# BrushlessDriver.net
KiCad netlist of a schematic drawn in Altium Designer
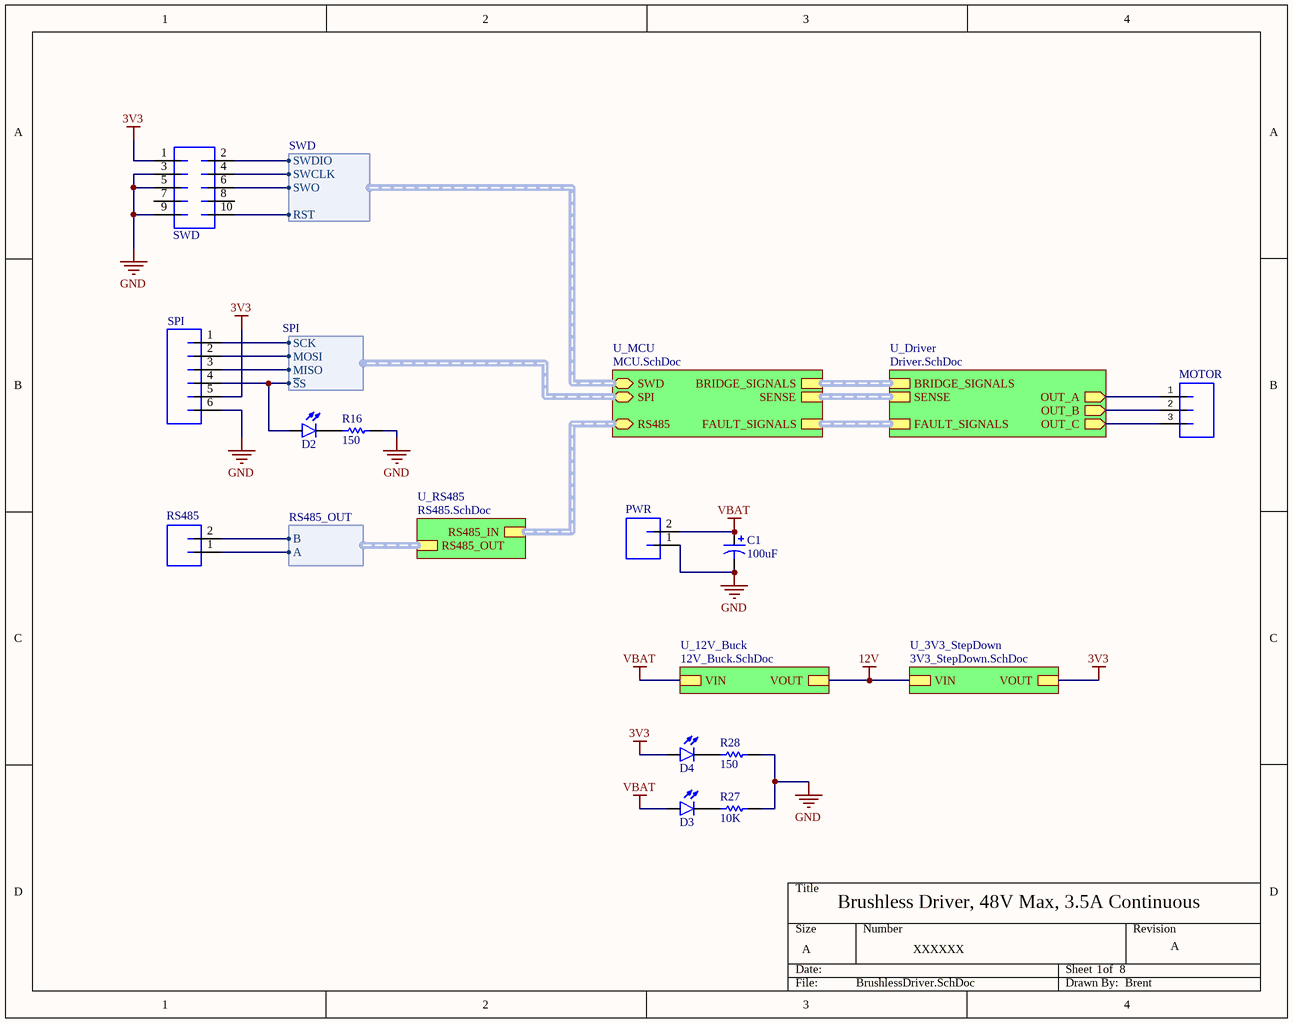
[diagram p0: BrushlessDriver.SchDoc]

(export (version "E")
  (design (tool "Eeschema 10.0.6"))
  (components
    (comp (ref "C1")
      (value "100uF")
      (footprint "CAP-ELECTROLYTIC[10.0x12.6]")
      (description "100uF 63V 20%")
      (fields (field (name "PARTNUMBER") "PCR1J101MCL1GS") (field (name "MANUFACTURER") "Nichicon"))
      (libsource (lib "Capacitors") (part "CAP_100uF_63V_20%"))
    )
    (comp (ref "D2")
      (value "LED_0603_GREEN_5mA")
      (footprint "LED0603")
      (fields (field (name "PARTNUMBER") "LTST-C193TGKT-5A") (field (name "MANUFACTURER") "Lite-On Inc."))
      (libsource (lib "LEDs") (part "LED_0603_GREEN_5mA"))
    )
    (comp (ref "D3")
      (value "LED_0603_ORANGE_5mA")
      (footprint "LED0603")
      (fields (field (name "PARTNUMBER") "LTST-C193KFKT-5A") (field (name "MANUFACTURER") "Lite-On Inc."))
      (libsource (lib "LEDs") (part "LED_0603_ORANGE_5mA"))
    )
    (comp (ref "D4")
      (value "LED_0603_GREEN_5mA")
      (footprint "LED0603")
      (fields (field (name "PARTNUMBER") "LTST-C193TGKT-5A") (field (name "MANUFACTURER") "Lite-On Inc."))
      (libsource (lib "LEDs") (part "LED_0603_GREEN_5mA"))
    )
    (comp (ref "MOTOR")
      (value "MotorConnector")
      (footprint "MotorConnector")
      (libsource (lib "Components") (part "MotorConnector"))
    )
    (comp (ref "PWR")
      (value "MOLEX_MICROFIT_2_SMD_HORZ")
      (footprint "MOLEX-MICROFIT-2-SMD-HORZ")
      (fields (field (name "MANUFACTURER") "Molex") (field (name "PARTNUMBER") "43650-0212"))
      (libsource (lib "Connectors") (part "MOLEX_MICROFIT_2_SMD_HORZ"))
    )
    (comp (ref "R16")
      (value "150")
      (footprint "RESC0603(1608)_L")
      (description "150R 0.1W 1% 0603 (1608 Metric)  SMD")
      (fields (field (name "TOLERANCE") "1 %") (field (name "POWER") "0.1 W"))
      (libsource (lib "Altium Content Vault") (part "CMP-1012-00415-1"))
    )
    (comp (ref "R27")
      (value "10K")
      (footprint "RESC0603(1608)_M")
      (description "10K 0.1W 1% 0603 (1608 Metric)  SMD")
      (fields (field (name "POWER") "0.1 W") (field (name "TOLERANCE") "1 %"))
      (libsource (lib "Altium Content Vault") (part "RES"))
    )
    (comp (ref "R28")
      (value "150")
      (footprint "RESC0603(1608)_L")
      (description "150R 0.1W 1% 0603 (1608 Metric)  SMD")
      (fields (field (name "TOLERANCE") "1 %") (field (name "POWER") "0.1 W"))
      (libsource (lib "Altium Content Vault") (part "CMP-1012-00415-1"))
    )
    (comp (ref "RS485")
      (value "JST_PH_2_VERT")
      (footprint "JST-PH-2-PTH-VERT")
      (fields
        (field (name "MANUFACTURER") "JST Sales America, Inc.")
        (field (name "PARTNUMBER") "B2B-PH-K-S(LF)(SN)")
      )
      (libsource (lib "Connectors") (part "JST_PH_2_VERT"))
    )
    (comp (ref "SPI")
      (value "JST_PH_6_VERT")
      (footprint "JST-PH-6-PTH-VERT")
      (fields
        (field (name "PARTNUMBER") "B6B-PH-K-S(LF)(SN)")
        (field (name "MANUFACTURER") "JST Sales America Inc.")
      )
      (libsource (lib "Connectors") (part "JST_PH_6_VERT"))
    )
    (comp (ref "SWD")
      (value "1.27mm SWD Connector")
      (footprint "SWD-SMD")
      (fields (field (name "MANUFACTURER") "Samtec") (field (name "PARTNUMBER") "FTSH-105-01-F-DV"))
      (libsource (lib "Connectors-Other") (part "SWD"))
    )
  )
  (nets
    (net (code "4") (name "/A") (class "Default")
      (node (ref "RS485") (pin "1") (pinfunction "1_1") (pintype "passive"))
    )
    (net (code "5") (name "/B") (class "Default")
      (node (ref "RS485") (pin "2") (pinfunction "2_2") (pintype "passive"))
    )
    (net (code "8") (name "/MISO") (class "Default")
      (node (ref "SPI") (pin "3") (pinfunction "3_3") (pintype "passive"))
    )
    (net (code "9") (name "/MOSI") (class "Default")
      (node (ref "SPI") (pin "2") (pinfunction "2_2") (pintype "passive"))
    )
    (net (code "10") (name "/OUT_A") (class "Default")
      (node (ref "MOTOR") (pin "1") (pinfunction "1_1") (pintype "passive"))
    )
    (net (code "11") (name "/OUT_B") (class "Default")
      (node (ref "MOTOR") (pin "2") (pinfunction "2_2") (pintype "passive"))
    )
    (net (code "12") (name "/OUT_C") (class "Default")
      (node (ref "MOTOR") (pin "3") (pinfunction "3_3") (pintype "passive"))
    )
    (net (code "14") (name "/RST") (class "Default")
      (node (ref "SWD") (pin "10") (pinfunction "10_10") (pintype "passive"))
    )
    (net (code "15") (name "/SCK") (class "Default")
      (node (ref "SPI") (pin "1") (pinfunction "1_1") (pintype "passive"))
    )
    (net (code "17") (name "/SWCLK") (class "Default")
      (node (ref "SWD") (pin "4") (pinfunction "4_4") (pintype "passive"))
    )
    (net (code "18") (name "/SWDIO") (class "Default")
      (node (ref "SWD") (pin "2") (pinfunction "2_2") (pintype "passive"))
    )
    (net (code "19") (name "/SWO") (class "Default")
      (node (ref "SWD") (pin "6") (pinfunction "6_6") (pintype "passive"))
    )
    (net (code "23") (name "/~{S}S") (class "Default")
      (node (ref "D2") (pin "A") (pinfunction "A_A") (pintype "passive"))
      (node (ref "SPI") (pin "4") (pinfunction "4_4") (pintype "passive"))
    )
    (net (code "24") (name "3V3") (class "Default")
      (node (ref "D4") (pin "A") (pinfunction "A_A") (pintype "passive"))
      (node (ref "SPI") (pin "5") (pinfunction "5_5") (pintype "passive"))
      (node (ref "SWD") (pin "1") (pinfunction "1_1") (pintype "passive"))
    )
    (net (code "26") (name "GND") (class "Default")
      (node (ref "C1") (pin "2") (pinfunction "2_2") (pintype "passive"))
      (node (ref "PWR") (pin "1") (pinfunction "1_1") (pintype "passive"))
      (node (ref "R16") (pin "1") (pinfunction "1_1") (pintype "passive"))
      (node (ref "R27") (pin "2") (pinfunction "2_2") (pintype "passive"))
      (node (ref "R28") (pin "1") (pinfunction "1_1") (pintype "passive"))
      (node (ref "SPI") (pin "6") (pinfunction "6_6") (pintype "passive"))
      (node (ref "SWD") (pin "3") (pinfunction "3_3") (pintype "passive"))
      (node (ref "SWD") (pin "5") (pinfunction "5_5") (pintype "passive"))
      (node (ref "SWD") (pin "9") (pinfunction "9_9") (pintype "passive"))
    )
    (net (code "27") (name "Net-(D2-PadC)") (class "Default")
      (node (ref "D2") (pin "C") (pinfunction "C_C") (pintype "passive"))
      (node (ref "R16") (pin "2") (pinfunction "2_2") (pintype "passive"))
    )
    (net (code "28") (name "Net-(D3-PadC)") (class "Default")
      (node (ref "D3") (pin "C") (pinfunction "C_C") (pintype "passive"))
      (node (ref "R27") (pin "1") (pinfunction "1_1") (pintype "passive"))
    )
    (net (code "29") (name "Net-(D4-PadC)") (class "Default")
      (node (ref "D4") (pin "C") (pinfunction "C_C") (pintype "passive"))
      (node (ref "R28") (pin "2") (pinfunction "2_2") (pintype "passive"))
    )
    (net (code "30") (name "VBAT") (class "Default")
      (node (ref "C1") (pin "1") (pinfunction "1_1") (pintype "passive"))
      (node (ref "D3") (pin "A") (pinfunction "A_A") (pintype "passive"))
      (node (ref "PWR") (pin "2") (pinfunction "2_2") (pintype "passive"))
    )
    (net (code "31") (name "unconnected-(SWD-Pad7)") (class "Default")
      (node (ref "SWD") (pin "7") (pinfunction "7_7") (pintype "passive"))
    )
    (net (code "32") (name "unconnected-(SWD-Pad8)") (class "Default")
      (node (ref "SWD") (pin "8") (pinfunction "8_8") (pintype "passive"))
    )
  )
)
